# mSD-Bee_v10.net
KiCad netlist of a schematic drawn in EAGLE
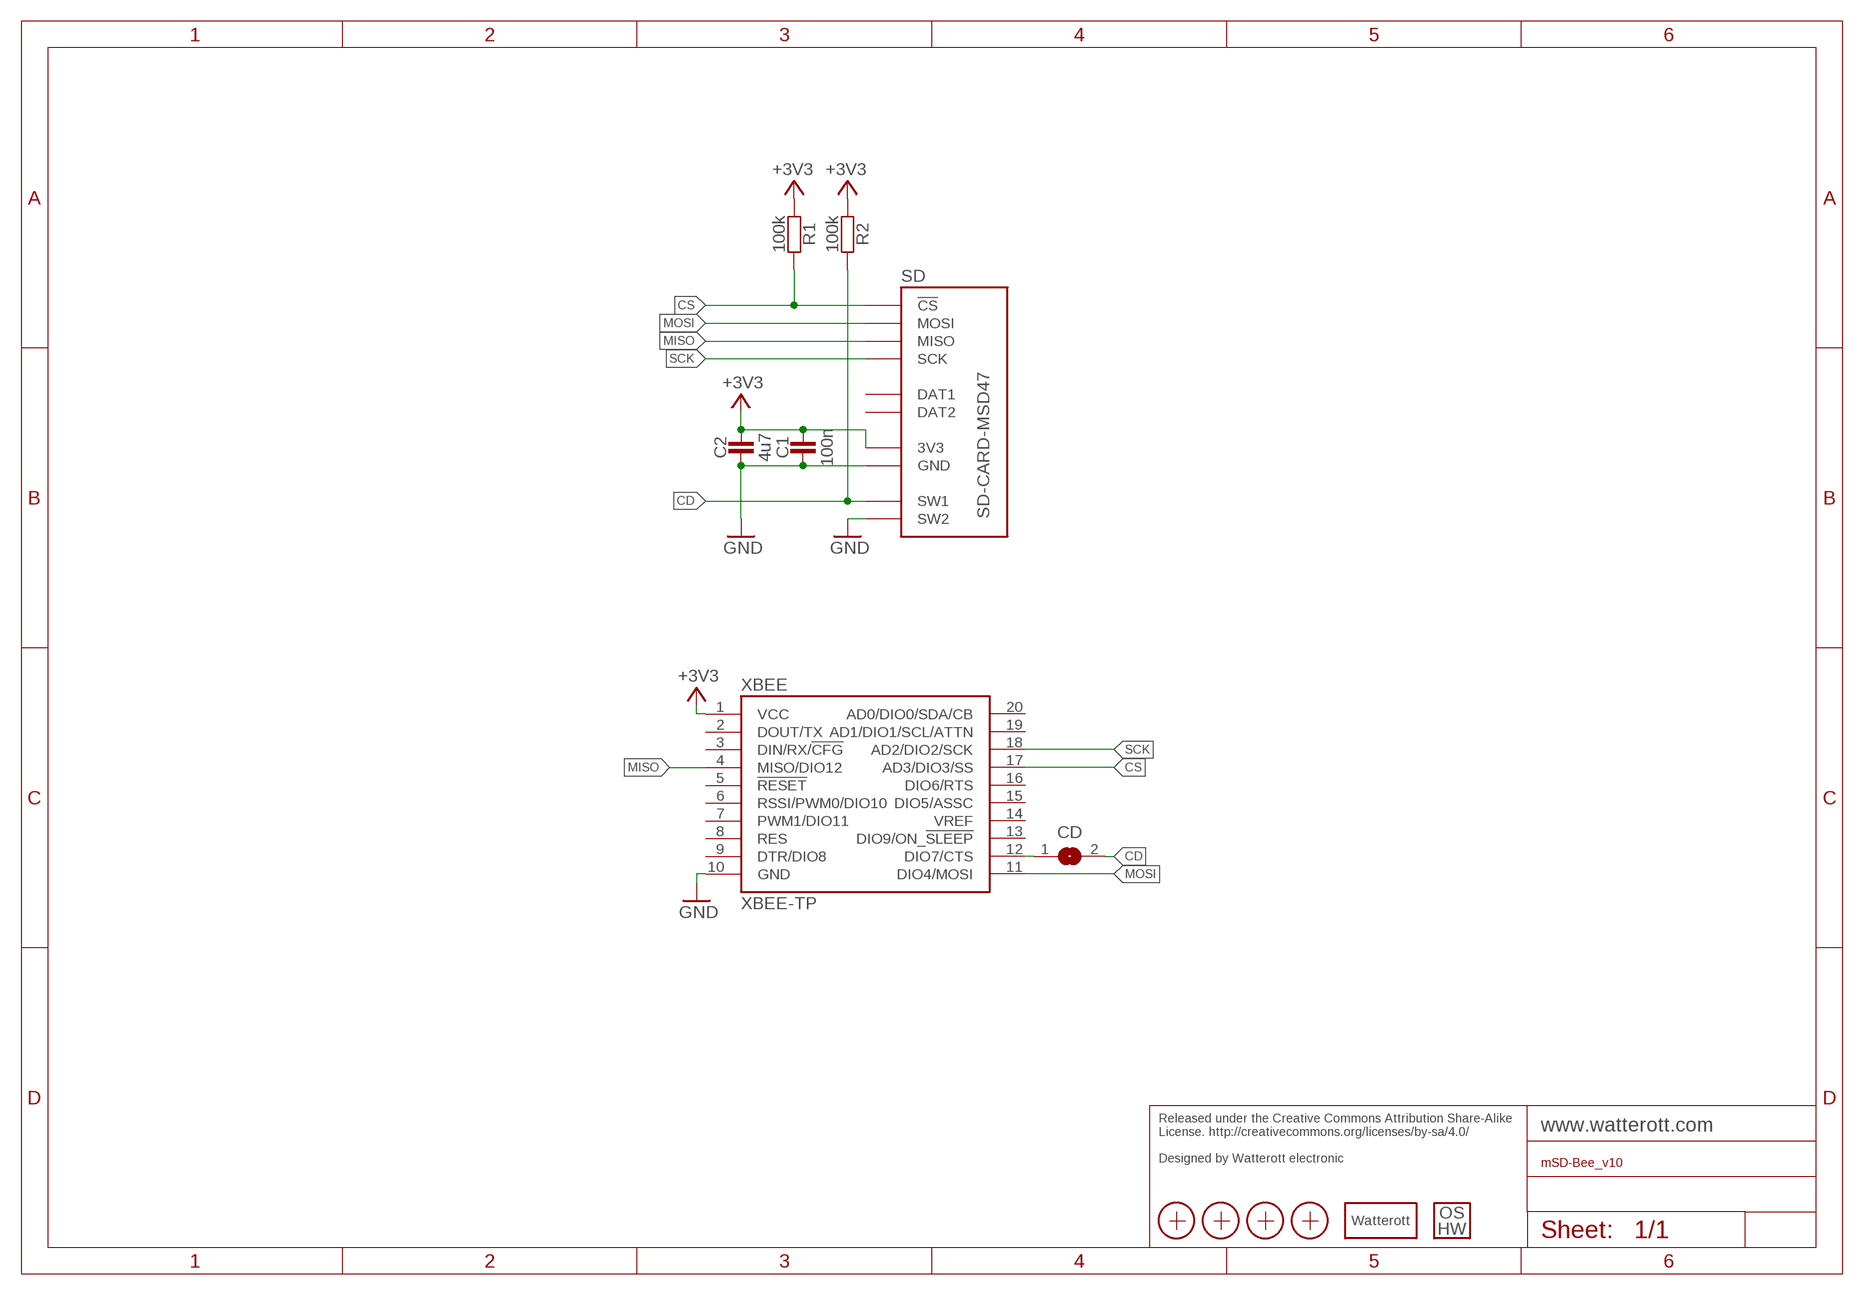
[diagram p0: schematic, sheet 1]

(export (version "E")
  (design (tool "Eeschema 10.0.6"))
  (components
    (comp (ref "C1")
      (value "100n")
      (footprint "eagle-import:C0402")
      (libsource (lib "eagle-import") (part "CAPACITOR-0402"))
    )
    (comp (ref "C2")
      (value "4u7")
      (footprint "eagle-import:C0603")
      (libsource (lib "eagle-import") (part "CAPACITOR-0603"))
    )
    (comp (ref "CD")
      (value "JUMPER2-0603")
      (footprint "eagle-import:JUMPER2-0603")
      (libsource (lib "eagle-import") (part "JUMPER2-0603"))
    )
    (comp (ref "LOGO3")
      (value "LOGO_SPARK-2")
      (footprint "eagle-import:SPARK_2MM")
      (libsource (lib "eagle-import") (part "LOGO_SPARK-2"))
    )
    (comp (ref "LOGO4")
      (value "LOGO_OSHW-2")
      (footprint "eagle-import:OSHW_2MM")
      (libsource (lib "eagle-import") (part "LOGO_OSHW-2"))
    )
    (comp (ref "R1")
      (value "100k")
      (footprint "eagle-import:C0402")
      (libsource (lib "eagle-import") (part "RESISTOR-0402"))
    )
    (comp (ref "R2")
      (value "100k")
      (footprint "eagle-import:C0402")
      (libsource (lib "eagle-import") (part "RESISTOR-0402"))
    )
    (comp (ref "SD")
      (value "SD-CARD-MSD47")
      (footprint "eagle-import:SD_47309XXXX")
      (libsource (lib "eagle-import") (part "SD-CARD-MSD47"))
    )
    (comp (ref "X1")
      (value "PASSER-07")
      (footprint "eagle-import:PASSER_07MM")
      (libsource (lib "eagle-import") (part "PASSER-07"))
    )
    (comp (ref "X2")
      (value "PASSER-07")
      (footprint "eagle-import:PASSER_07MM")
      (libsource (lib "eagle-import") (part "PASSER-07"))
    )
    (comp (ref "X3")
      (value "PASSER-07")
      (footprint "eagle-import:PASSER_07MM")
      (libsource (lib "eagle-import") (part "PASSER-07"))
    )
    (comp (ref "X4")
      (value "PASSER-07")
      (footprint "eagle-import:PASSER_07MM")
      (libsource (lib "eagle-import") (part "PASSER-07"))
    )
    (comp (ref "XBEE")
      (value "XBEE-TP")
      (footprint "eagle-import:XBEE_TP")
      (libsource (lib "eagle-import") (part "XBEE-TP"))
    )
  )
  (nets
    (net (code "1") (name "+3V3") (class "Default")
      (node (ref "C1") (pin "2") (pinfunction "2_2") (pintype "passive"))
      (node (ref "C2") (pin "2") (pinfunction "2_2") (pintype "passive"))
      (node (ref "R1") (pin "2") (pinfunction "2_2") (pintype "passive"))
      (node (ref "R2") (pin "2") (pinfunction "2_2") (pintype "passive"))
      (node (ref "SD") (pin "VCC") (pinfunction "3V3_VCC") (pintype "bidirectional"))
      (node (ref "XBEE") (pin "1") (pinfunction "VCC_1") (pintype "power_in"))
    )
    (net (code "2") (name "CD") (class "Default")
      (node (ref "CD") (pin "2") (pinfunction "2_2") (pintype "passive"))
      (node (ref "R2") (pin "1") (pinfunction "1_1") (pintype "passive"))
      (node (ref "SD") (pin "SW1") (pinfunction "SW1_SW1") (pintype "bidirectional"))
    )
    (net (code "3") (name "CS") (class "Default")
      (node (ref "R1") (pin "1") (pinfunction "1_1") (pintype "passive"))
      (node (ref "SD") (pin "CS") (pinfunction "~{CS}_CS") (pintype "bidirectional"))
      (node (ref "XBEE") (pin "17") (pinfunction "AD3/DIO3/SS_17") (pintype "bidirectional"))
    )
    (net (code "4") (name "GND") (class "Default")
      (node (ref "C1") (pin "1") (pinfunction "1_1") (pintype "passive"))
      (node (ref "C2") (pin "1") (pinfunction "1_1") (pintype "passive"))
      (node (ref "SD") (pin "GND") (pinfunction "GND_GND") (pintype "bidirectional"))
      (node (ref "SD") (pin "GND@1") (pinfunction "GND_GND@1") (pintype "bidirectional"))
      (node (ref "SD") (pin "GND@2") (pinfunction "GND_GND@2") (pintype "bidirectional"))
      (node (ref "SD") (pin "SW2") (pinfunction "SW2_SW2") (pintype "bidirectional"))
      (node (ref "XBEE") (pin "10") (pinfunction "GND_10") (pintype "power_in"))
    )
    (net (code "5") (name "MISO") (class "Default")
      (node (ref "SD") (pin "MISO") (pinfunction "MISO_MISO") (pintype "bidirectional"))
      (node (ref "XBEE") (pin "4") (pinfunction "MISO/DIO12_4") (pintype "bidirectional"))
    )
    (net (code "6") (name "MOSI") (class "Default")
      (node (ref "SD") (pin "MOSI") (pinfunction "MOSI_MOSI") (pintype "bidirectional"))
      (node (ref "XBEE") (pin "11") (pinfunction "DIO4/MOSI_11") (pintype "bidirectional"))
    )
    (net (code "7") (name "Net-(XBEE-DIO7{slash}CTS)") (class "Default")
      (node (ref "CD") (pin "1") (pinfunction "1_1") (pintype "passive"))
      (node (ref "XBEE") (pin "12") (pinfunction "DIO7/CTS_12") (pintype "bidirectional"))
    )
    (net (code "8") (name "SCK") (class "Default")
      (node (ref "SD") (pin "SCK") (pinfunction "SCK_SCK") (pintype "bidirectional"))
      (node (ref "XBEE") (pin "18") (pinfunction "AD2/DIO2/SCK_18") (pintype "bidirectional"))
    )
    (net (code "9") (name "unconnected-(SD-PadDAT1)") (class "Default")
      (node (ref "SD") (pin "DAT1") (pinfunction "DAT1_DAT1") (pintype "bidirectional"))
    )
    (net (code "10") (name "unconnected-(SD-PadDAT2)") (class "Default")
      (node (ref "SD") (pin "DAT2") (pinfunction "DAT2_DAT2") (pintype "bidirectional"))
    )
    (net (code "11") (name "unconnected-(XBEE-AD0{slash}DIO0{slash}SDA{slash}CB-Pad20)") (class "Default")
      (node (ref "XBEE") (pin "20") (pinfunction "AD0/DIO0/SDA/CB_20") (pintype "bidirectional"))
    )
    (net (code "12") (name "unconnected-(XBEE-AD1{slash}DIO1{slash}SCL{slash}ATTN-Pad19)") (class "Default")
      (node (ref "XBEE") (pin "19") (pinfunction "AD1/DIO1/SCL/ATTN_19") (pintype "bidirectional"))
    )
    (net (code "13") (name "unconnected-(XBEE-DIN{slash}RX{slash}~{CFG}-Pad3)") (class "Default")
      (node (ref "XBEE") (pin "3") (pinfunction "DIN/RX/~{CFG}_3") (pintype "bidirectional"))
    )
    (net (code "14") (name "unconnected-(XBEE-DIO5{slash}ASSC-Pad15)") (class "Default")
      (node (ref "XBEE") (pin "15") (pinfunction "DIO5/ASSC_15") (pintype "bidirectional"))
    )
    (net (code "15") (name "unconnected-(XBEE-DIO6{slash}RTS-Pad16)") (class "Default")
      (node (ref "XBEE") (pin "16") (pinfunction "DIO6/RTS_16") (pintype "bidirectional"))
    )
    (net (code "16") (name "unconnected-(XBEE-DIO9{slash}ON_~{SLEEP}-Pad13)") (class "Default")
      (node (ref "XBEE") (pin "13") (pinfunction "DIO9/ON_~{SLEEP}_13") (pintype "bidirectional"))
    )
    (net (code "17") (name "unconnected-(XBEE-DOUT{slash}TX-Pad2)") (class "Default")
      (node (ref "XBEE") (pin "2") (pinfunction "DOUT/TX_2") (pintype "bidirectional"))
    )
    (net (code "18") (name "unconnected-(XBEE-DTR{slash}DIO8-Pad9)") (class "Default")
      (node (ref "XBEE") (pin "9") (pinfunction "DTR/DIO8_9") (pintype "bidirectional"))
    )
    (net (code "19") (name "unconnected-(XBEE-PWM1{slash}DIO11-Pad7)") (class "Default")
      (node (ref "XBEE") (pin "7") (pinfunction "PWM1/DIO11_7") (pintype "bidirectional"))
    )
    (net (code "20") (name "unconnected-(XBEE-RES-Pad8)") (class "Default")
      (node (ref "XBEE") (pin "8") (pinfunction "RES_8") (pintype "bidirectional"))
    )
    (net (code "21") (name "unconnected-(XBEE-RSSI{slash}PWM0{slash}DIO10-Pad6)") (class "Default")
      (node (ref "XBEE") (pin "6") (pinfunction "RSSI/PWM0/DIO10_6") (pintype "bidirectional"))
    )
    (net (code "22") (name "unconnected-(XBEE-VREF-Pad14)") (class "Default")
      (node (ref "XBEE") (pin "14") (pinfunction "VREF_14") (pintype "bidirectional"))
    )
    (net (code "23") (name "unconnected-(XBEE-~{RESET}-Pad5)") (class "Default")
      (node (ref "XBEE") (pin "5") (pinfunction "~{RESET}_5") (pintype "bidirectional"))
    )
  )
)
